# shield.net
KiCad netlist of a schematic drawn in EAGLE
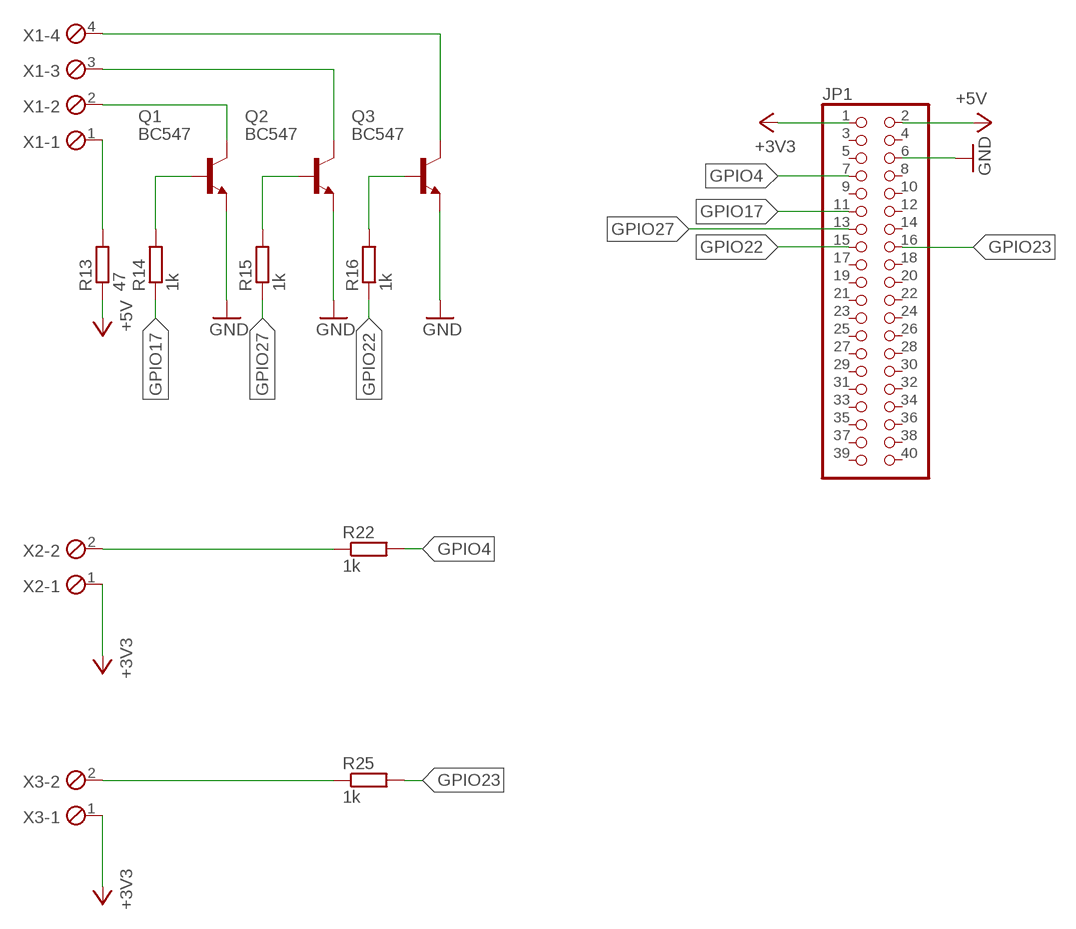
[diagram p0: schematic, sheet 1]

(export (version "E")
  (design (tool "Eeschema 10.0.6"))
  (components
    (comp (ref "JP1")
      (value "PINHD-2X20")
      (footprint "eagle-import:2X20")
      (libsource (lib "eagle-import") (part "PINHD-2X20"))
    )
    (comp (ref "Q1")
      (value "BC547")
      (footprint "eagle-import:TO92")
      (libsource (lib "eagle-import") (part "BC547"))
    )
    (comp (ref "Q2")
      (value "BC547")
      (footprint "eagle-import:TO92")
      (libsource (lib "eagle-import") (part "BC547"))
    )
    (comp (ref "Q3")
      (value "BC547")
      (footprint "eagle-import:TO92")
      (libsource (lib "eagle-import") (part "BC547"))
    )
    (comp (ref "R13")
      (value "47")
      (footprint "eagle-import:0204_7")
      (libsource (lib "eagle-import") (part "R-EU_0204/7"))
    )
    (comp (ref "R14")
      (value "1k")
      (footprint "eagle-import:0204_5")
      (libsource (lib "eagle-import") (part "R-EU_0204/5"))
    )
    (comp (ref "R15")
      (value "1k")
      (footprint "eagle-import:0204_7")
      (libsource (lib "eagle-import") (part "R-EU_0204/7"))
    )
    (comp (ref "R16")
      (value "1k")
      (footprint "eagle-import:0204_7")
      (libsource (lib "eagle-import") (part "R-EU_0204/7"))
    )
    (comp (ref "R22")
      (value "1k")
      (footprint "eagle-import:0204_7")
      (libsource (lib "eagle-import") (part "R-EU_0204/7"))
    )
    (comp (ref "R25")
      (value "1k")
      (footprint "eagle-import:0204_7")
      (libsource (lib "eagle-import") (part "R-EU_0204/7"))
    )
    (comp (ref "X1")
      (value "MPT4")
      (footprint "eagle-import:4POL254")
      (libsource (lib "eagle-import") (part "MPT4"))
    )
    (comp (ref "X2")
      (value "MPT2")
      (footprint "eagle-import:2POL254")
      (libsource (lib "eagle-import") (part "MPT2"))
    )
    (comp (ref "X3")
      (value "MPT2")
      (footprint "eagle-import:2POL254")
      (libsource (lib "eagle-import") (part "MPT2"))
    )
  )
  (nets
    (net (code "1") (name "+3V3") (class "Default")
      (node (ref "JP1") (pin "1") (pinfunction "1_1") (pintype "passive"))
      (node (ref "X2") (pin "1") (pinfunction "1_1") (pintype "passive"))
      (node (ref "X3") (pin "1") (pinfunction "1_1") (pintype "passive"))
    )
    (net (code "2") (name "+5V") (class "Default")
      (node (ref "JP1") (pin "2") (pinfunction "2_2") (pintype "passive"))
      (node (ref "R13") (pin "1") (pinfunction "1_1") (pintype "passive"))
    )
    (net (code "3") (name "GND") (class "Default")
      (node (ref "JP1") (pin "6") (pinfunction "6_6") (pintype "passive"))
      (node (ref "Q1") (pin "1") (pinfunction "E_1") (pintype "passive"))
      (node (ref "Q2") (pin "1") (pinfunction "E_1") (pintype "passive"))
      (node (ref "Q3") (pin "1") (pinfunction "E_1") (pintype "passive"))
    )
    (net (code "4") (name "GPIO4") (class "Default")
      (node (ref "JP1") (pin "7") (pinfunction "7_7") (pintype "passive"))
      (node (ref "R22") (pin "2") (pinfunction "2_2") (pintype "passive"))
    )
    (net (code "5") (name "GPIO17") (class "Default")
      (node (ref "JP1") (pin "11") (pinfunction "11_11") (pintype "passive"))
      (node (ref "R14") (pin "1") (pinfunction "1_1") (pintype "passive"))
    )
    (net (code "6") (name "GPIO22") (class "Default")
      (node (ref "JP1") (pin "15") (pinfunction "15_15") (pintype "passive"))
      (node (ref "R16") (pin "1") (pinfunction "1_1") (pintype "passive"))
    )
    (net (code "7") (name "GPIO23") (class "Default")
      (node (ref "JP1") (pin "16") (pinfunction "16_16") (pintype "passive"))
      (node (ref "R25") (pin "2") (pinfunction "2_2") (pintype "passive"))
    )
    (net (code "8") (name "GPIO27") (class "Default")
      (node (ref "JP1") (pin "13") (pinfunction "13_13") (pintype "passive"))
      (node (ref "R15") (pin "1") (pinfunction "1_1") (pintype "passive"))
    )
    (net (code "9") (name "Net-(Q1-B)") (class "Default")
      (node (ref "Q1") (pin "2") (pinfunction "B_2") (pintype "passive"))
      (node (ref "R14") (pin "2") (pinfunction "2_2") (pintype "passive"))
    )
    (net (code "10") (name "Net-(Q1-C)") (class "Default")
      (node (ref "Q1") (pin "3") (pinfunction "C_3") (pintype "passive"))
      (node (ref "X1") (pin "2") (pinfunction "1_2") (pintype "passive"))
    )
    (net (code "11") (name "Net-(Q2-B)") (class "Default")
      (node (ref "Q2") (pin "2") (pinfunction "B_2") (pintype "passive"))
      (node (ref "R15") (pin "2") (pinfunction "2_2") (pintype "passive"))
    )
    (net (code "12") (name "Net-(Q2-C)") (class "Default")
      (node (ref "Q2") (pin "3") (pinfunction "C_3") (pintype "passive"))
      (node (ref "X1") (pin "3") (pinfunction "1_3") (pintype "passive"))
    )
    (net (code "13") (name "Net-(Q3-B)") (class "Default")
      (node (ref "Q3") (pin "2") (pinfunction "B_2") (pintype "passive"))
      (node (ref "R16") (pin "2") (pinfunction "2_2") (pintype "passive"))
    )
    (net (code "14") (name "Net-(Q3-C)") (class "Default")
      (node (ref "Q3") (pin "3") (pinfunction "C_3") (pintype "passive"))
      (node (ref "X1") (pin "4") (pinfunction "1_4") (pintype "passive"))
    )
    (net (code "15") (name "Net-(R13-Pad2)") (class "Default")
      (node (ref "R13") (pin "2") (pinfunction "2_2") (pintype "passive"))
      (node (ref "X1") (pin "1") (pinfunction "1_1") (pintype "passive"))
    )
    (net (code "16") (name "Net-(X2B-1)") (class "Default")
      (node (ref "R22") (pin "1") (pinfunction "1_1") (pintype "passive"))
      (node (ref "X2") (pin "2") (pinfunction "1_2") (pintype "passive"))
    )
    (net (code "17") (name "Net-(X3B-1)") (class "Default")
      (node (ref "R25") (pin "1") (pinfunction "1_1") (pintype "passive"))
      (node (ref "X3") (pin "2") (pinfunction "1_2") (pintype "passive"))
    )
    (net (code "18") (name "unconnected-(JP1-Pad3)") (class "Default")
      (node (ref "JP1") (pin "3") (pinfunction "3_3") (pintype "passive"))
    )
    (net (code "19") (name "unconnected-(JP1-Pad4)") (class "Default")
      (node (ref "JP1") (pin "4") (pinfunction "4_4") (pintype "passive"))
    )
    (net (code "20") (name "unconnected-(JP1-Pad5)") (class "Default")
      (node (ref "JP1") (pin "5") (pinfunction "5_5") (pintype "passive"))
    )
    (net (code "21") (name "unconnected-(JP1-Pad8)") (class "Default")
      (node (ref "JP1") (pin "8") (pinfunction "8_8") (pintype "passive"))
    )
    (net (code "22") (name "unconnected-(JP1-Pad9)") (class "Default")
      (node (ref "JP1") (pin "9") (pinfunction "9_9") (pintype "passive"))
    )
    (net (code "23") (name "unconnected-(JP1-Pad10)") (class "Default")
      (node (ref "JP1") (pin "10") (pinfunction "10_10") (pintype "passive"))
    )
    (net (code "24") (name "unconnected-(JP1-Pad12)") (class "Default")
      (node (ref "JP1") (pin "12") (pinfunction "12_12") (pintype "passive"))
    )
    (net (code "25") (name "unconnected-(JP1-Pad14)") (class "Default")
      (node (ref "JP1") (pin "14") (pinfunction "14_14") (pintype "passive"))
    )
    (net (code "26") (name "unconnected-(JP1-Pad17)") (class "Default")
      (node (ref "JP1") (pin "17") (pinfunction "17_17") (pintype "passive"))
    )
    (net (code "27") (name "unconnected-(JP1-Pad18)") (class "Default")
      (node (ref "JP1") (pin "18") (pinfunction "18_18") (pintype "passive"))
    )
    (net (code "28") (name "unconnected-(JP1-Pad19)") (class "Default")
      (node (ref "JP1") (pin "19") (pinfunction "19_19") (pintype "passive"))
    )
    (net (code "29") (name "unconnected-(JP1-Pad20)") (class "Default")
      (node (ref "JP1") (pin "20") (pinfunction "20_20") (pintype "passive"))
    )
    (net (code "30") (name "unconnected-(JP1-Pad21)") (class "Default")
      (node (ref "JP1") (pin "21") (pinfunction "21_21") (pintype "passive"))
    )
    (net (code "31") (name "unconnected-(JP1-Pad22)") (class "Default")
      (node (ref "JP1") (pin "22") (pinfunction "22_22") (pintype "passive"))
    )
    (net (code "32") (name "unconnected-(JP1-Pad23)") (class "Default")
      (node (ref "JP1") (pin "23") (pinfunction "23_23") (pintype "passive"))
    )
    (net (code "33") (name "unconnected-(JP1-Pad24)") (class "Default")
      (node (ref "JP1") (pin "24") (pinfunction "24_24") (pintype "passive"))
    )
    (net (code "34") (name "unconnected-(JP1-Pad25)") (class "Default")
      (node (ref "JP1") (pin "25") (pinfunction "25_25") (pintype "passive"))
    )
    (net (code "35") (name "unconnected-(JP1-Pad26)") (class "Default")
      (node (ref "JP1") (pin "26") (pinfunction "26_26") (pintype "passive"))
    )
    (net (code "36") (name "unconnected-(JP1-Pad27)") (class "Default")
      (node (ref "JP1") (pin "27") (pinfunction "27_27") (pintype "passive"))
    )
    (net (code "37") (name "unconnected-(JP1-Pad28)") (class "Default")
      (node (ref "JP1") (pin "28") (pinfunction "28_28") (pintype "passive"))
    )
    (net (code "38") (name "unconnected-(JP1-Pad29)") (class "Default")
      (node (ref "JP1") (pin "29") (pinfunction "29_29") (pintype "passive"))
    )
    (net (code "39") (name "unconnected-(JP1-Pad30)") (class "Default")
      (node (ref "JP1") (pin "30") (pinfunction "30_30") (pintype "passive"))
    )
    (net (code "40") (name "unconnected-(JP1-Pad31)") (class "Default")
      (node (ref "JP1") (pin "31") (pinfunction "31_31") (pintype "passive"))
    )
    (net (code "41") (name "unconnected-(JP1-Pad32)") (class "Default")
      (node (ref "JP1") (pin "32") (pinfunction "32_32") (pintype "passive"))
    )
    (net (code "42") (name "unconnected-(JP1-Pad33)") (class "Default")
      (node (ref "JP1") (pin "33") (pinfunction "33_33") (pintype "passive"))
    )
    (net (code "43") (name "unconnected-(JP1-Pad34)") (class "Default")
      (node (ref "JP1") (pin "34") (pinfunction "34_34") (pintype "passive"))
    )
    (net (code "44") (name "unconnected-(JP1-Pad35)") (class "Default")
      (node (ref "JP1") (pin "35") (pinfunction "35_35") (pintype "passive"))
    )
    (net (code "45") (name "unconnected-(JP1-Pad36)") (class "Default")
      (node (ref "JP1") (pin "36") (pinfunction "36_36") (pintype "passive"))
    )
    (net (code "46") (name "unconnected-(JP1-Pad37)") (class "Default")
      (node (ref "JP1") (pin "37") (pinfunction "37_37") (pintype "passive"))
    )
    (net (code "47") (name "unconnected-(JP1-Pad38)") (class "Default")
      (node (ref "JP1") (pin "38") (pinfunction "38_38") (pintype "passive"))
    )
    (net (code "48") (name "unconnected-(JP1-Pad39)") (class "Default")
      (node (ref "JP1") (pin "39") (pinfunction "39_39") (pintype "passive"))
    )
    (net (code "49") (name "unconnected-(JP1-Pad40)") (class "Default")
      (node (ref "JP1") (pin "40") (pinfunction "40_40") (pintype "passive"))
    )
  )
)
